# Board-ADC.net
KiCad netlist of a schematic drawn in Altium Designer
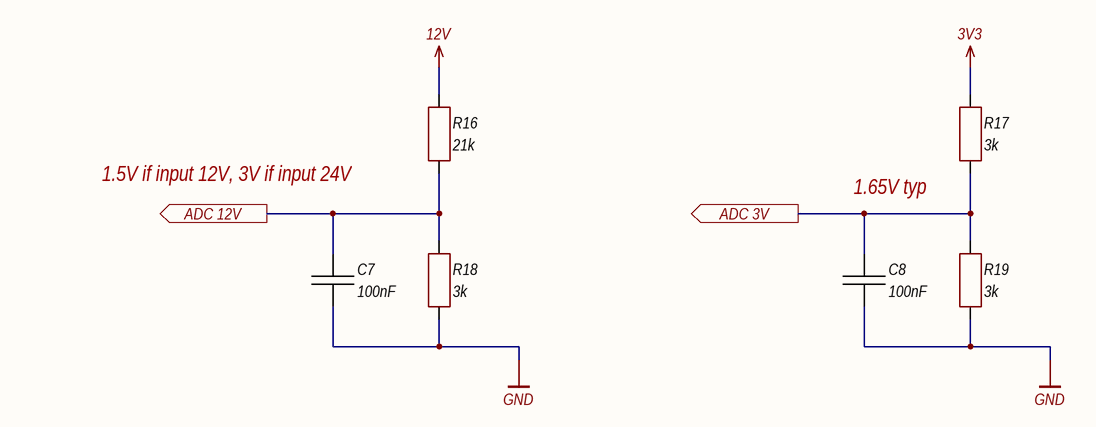
[diagram p0: Board-ADC.SchDoc]

(export (version "E")
  (design (tool "Eeschema 10.0.6"))
  (components
    (comp (ref "C7")
      (value "100nF")
      (footprint "CH0402C")
      (fields (field (name "MANUFACTURER") "CCTC"))
      (libsource (lib "Discrete") (part "Capacitor"))
    )
    (comp (ref "C8")
      (value "100nF")
      (footprint "CH0402C")
      (fields (field (name "MANUFACTURER") "CCTC"))
      (libsource (lib "Discrete") (part "Capacitor"))
    )
    (comp (ref "R16")
      (value "21k")
      (footprint "CH0402R")
      (fields (field (name "MANUFACTURER") "Uniroyal Elec"))
      (libsource (lib "Discrete") (part "Resistor"))
    )
    (comp (ref "R17")
      (value "3k")
      (footprint "CH0402R")
      (fields (field (name "MANUFACTURER") "Uniroyal Elec"))
      (libsource (lib "Discrete") (part "Resistor"))
    )
    (comp (ref "R18")
      (value "3k")
      (footprint "CH0402R")
      (fields (field (name "MANUFACTURER") "Uniroyal Elec"))
      (libsource (lib "Discrete") (part "Resistor"))
    )
    (comp (ref "R19")
      (value "3k")
      (footprint "CH0402R")
      (fields (field (name "MANUFACTURER") "Uniroyal Elec"))
      (libsource (lib "Discrete") (part "Resistor"))
    )
  )
  (nets
    (net (code "1") (name "/ADC 3V") (class "Default")
      (node (ref "C8") (pin "2") (pinfunction "2_2") (pintype "passive"))
      (node (ref "R17") (pin "1") (pinfunction "1_1") (pintype "passive"))
      (node (ref "R19") (pin "2") (pinfunction "2_2") (pintype "passive"))
    )
    (net (code "2") (name "/ADC 12V") (class "Default")
      (node (ref "C7") (pin "2") (pinfunction "2_2") (pintype "passive"))
      (node (ref "R16") (pin "1") (pinfunction "1_1") (pintype "passive"))
      (node (ref "R18") (pin "2") (pinfunction "2_2") (pintype "passive"))
    )
    (net (code "3") (name "3V3") (class "Default")
      (node (ref "R17") (pin "2") (pinfunction "2_2") (pintype "passive"))
    )
    (net (code "4") (name "12V") (class "Default")
      (node (ref "R16") (pin "2") (pinfunction "2_2") (pintype "passive"))
    )
    (net (code "5") (name "GND") (class "Default")
      (node (ref "C7") (pin "1") (pinfunction "1_1") (pintype "passive"))
      (node (ref "C8") (pin "1") (pinfunction "1_1") (pintype "passive"))
      (node (ref "R18") (pin "1") (pinfunction "1_1") (pintype "passive"))
      (node (ref "R19") (pin "1") (pinfunction "1_1") (pintype "passive"))
    )
  )
)
